# DSP_Block.net
KiCad netlist of a schematic drawn in Altium Designer
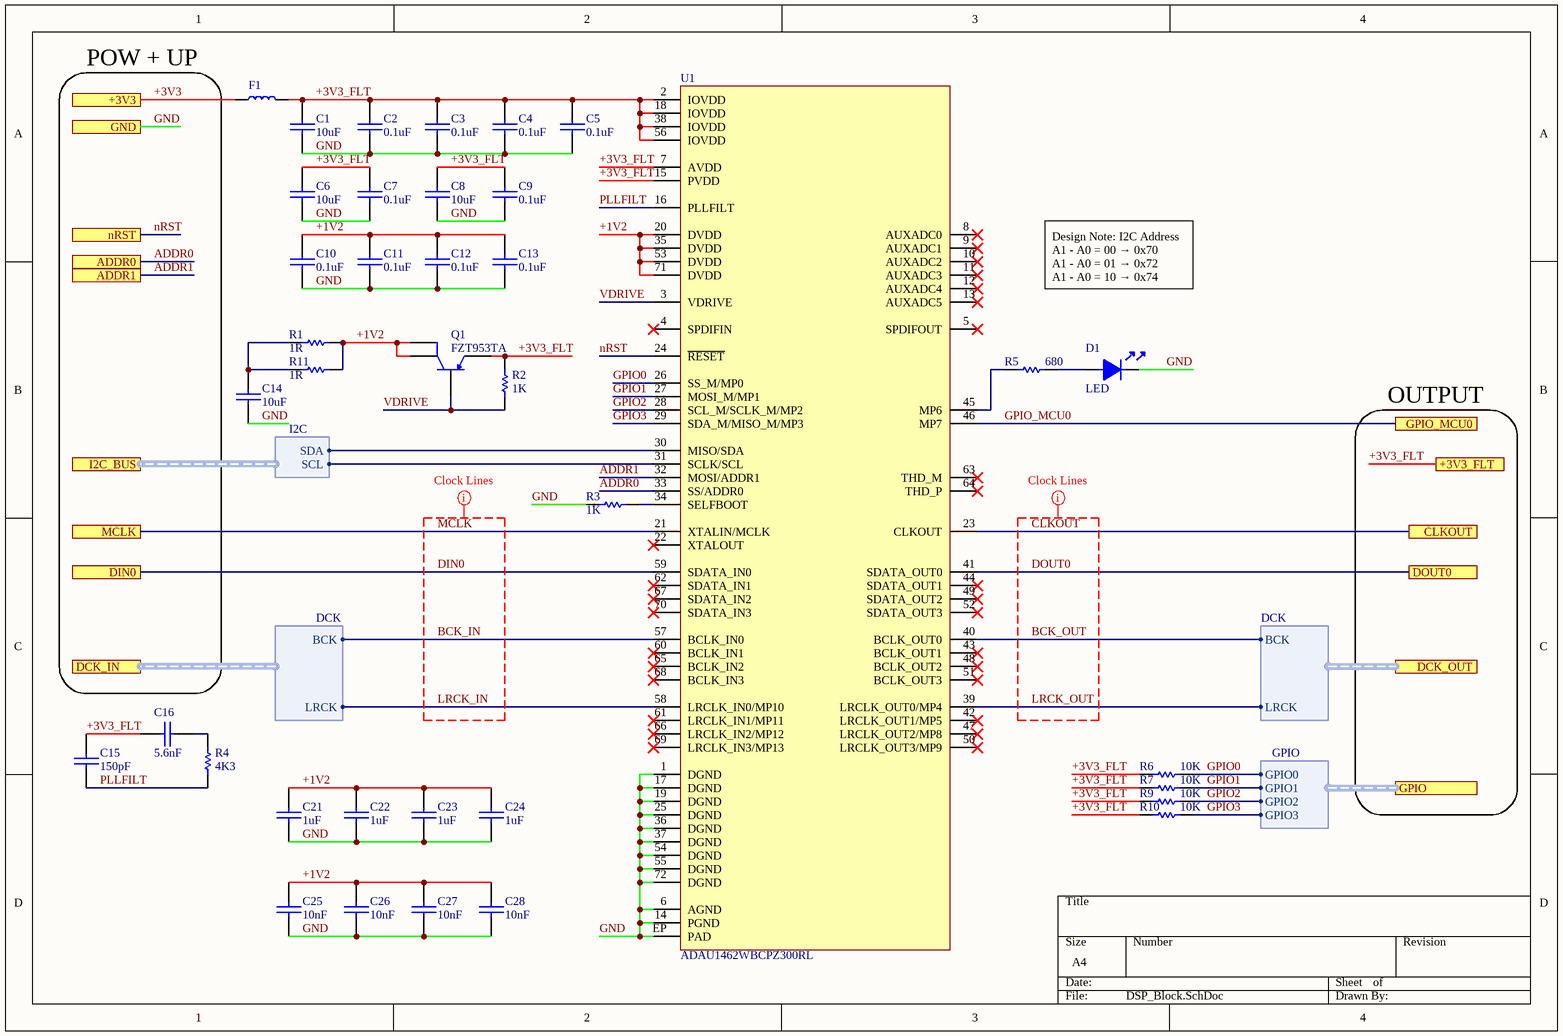
[diagram p0: DSP_Block.SchDoc]

(export (version "E")
  (design (tool "Eeschema 10.0.6"))
  (components
    (comp (ref "C1")
      (value "10uF")
      (footprint "0402-CAP-TDK")
      (fields (field (name "JLCPART") "C324476"))
      (libsource (lib "LIB2022 - Passives") (part "CAP-SMD"))
    )
    (comp (ref "C2")
      (value "0.1uF")
      (footprint "0402-CAP-TDK")
      (fields (field (name "JLCPART") "C307331"))
      (libsource (lib "LIB2022 - Passives") (part "CAP-SMD"))
    )
    (comp (ref "C3")
      (value "0.1uF")
      (footprint "0402-CAP-TDK")
      (fields (field (name "JLCPART") "C307331"))
      (libsource (lib "LIB2022 - Passives") (part "CAP-SMD"))
    )
    (comp (ref "C4")
      (value "0.1uF")
      (footprint "0402-CAP-TDK")
      (fields (field (name "JLCPART") "C307331"))
      (libsource (lib "LIB2022 - Passives") (part "CAP-SMD"))
    )
    (comp (ref "C5")
      (value "0.1uF")
      (footprint "0402-CAP-TDK")
      (fields (field (name "JLCPART") "C307331"))
      (libsource (lib "LIB2022 - Passives") (part "CAP-SMD"))
    )
    (comp (ref "C6")
      (value "10uF")
      (footprint "0402-CAP-TDK")
      (fields (field (name "JLCPART") "C324476"))
      (libsource (lib "LIB2022 - Passives") (part "CAP-SMD"))
    )
    (comp (ref "C7")
      (value "0.1uF")
      (footprint "0402-CAP-TDK")
      (fields (field (name "JLCPART") "C307331"))
      (libsource (lib "LIB2022 - Passives") (part "CAP-SMD"))
    )
    (comp (ref "C8")
      (value "10uF")
      (footprint "0402-CAP-TDK")
      (fields (field (name "JLCPART") "C324476"))
      (libsource (lib "LIB2022 - Passives") (part "CAP-SMD"))
    )
    (comp (ref "C9")
      (value "0.1uF")
      (footprint "0402-CAP-TDK")
      (fields (field (name "JLCPART") "C307331"))
      (libsource (lib "LIB2022 - Passives") (part "CAP-SMD"))
    )
    (comp (ref "C10")
      (value "0.1uF")
      (footprint "0402-CAP-TDK")
      (fields (field (name "JLCPART") "C307331"))
      (libsource (lib "LIB2022 - Passives") (part "CAP-SMD"))
    )
    (comp (ref "C11")
      (value "0.1uF")
      (footprint "0402-CAP-TDK")
      (fields (field (name "JLCPART") "C307331"))
      (libsource (lib "LIB2022 - Passives") (part "CAP-SMD"))
    )
    (comp (ref "C12")
      (value "0.1uF")
      (footprint "0402-CAP-TDK")
      (fields (field (name "JLCPART") "C307331"))
      (libsource (lib "LIB2022 - Passives") (part "CAP-SMD"))
    )
    (comp (ref "C13")
      (value "0.1uF")
      (footprint "0402-CAP-TDK")
      (fields (field (name "JLCPART") "C307331"))
      (libsource (lib "LIB2022 - Passives") (part "CAP-SMD"))
    )
    (comp (ref "C14")
      (value "10uF")
      (footprint "0402-CAP-TDK")
      (fields (field (name "JLCPART") "C324476"))
      (libsource (lib "LIB2022 - Passives") (part "CAP-SMD"))
    )
    (comp (ref "C15")
      (value "150pF")
      (footprint "0402-CAP-TDK")
      (fields (field (name "JLCPART") "C237333"))
      (libsource (lib "LIB2022 - Passives") (part "CAP-SMD"))
    )
    (comp (ref "C16")
      (value "5.6nF")
      (footprint "0402-CAP-TDK")
      (fields (field (name "JLCPART") "C513725"))
      (libsource (lib "LIB2022 - Passives") (part "CAP-SMD"))
    )
    (comp (ref "C21")
      (value "1uF")
      (footprint "0402-CAP-TDK")
      (fields (field (name "JLCPART") "C52923"))
      (libsource (lib "LIB2022 - Passives") (part "CAP-SMD"))
    )
    (comp (ref "C22")
      (value "1uF")
      (footprint "0402-CAP-TDK")
      (fields (field (name "JLCPART") "C52923"))
      (libsource (lib "LIB2022 - Passives") (part "CAP-SMD"))
    )
    (comp (ref "C23")
      (value "1uF")
      (footprint "0402-CAP-TDK")
      (fields (field (name "JLCPART") "C52923"))
      (libsource (lib "LIB2022 - Passives") (part "CAP-SMD"))
    )
    (comp (ref "C24")
      (value "1uF")
      (footprint "0402-CAP-TDK")
      (fields (field (name "JLCPART") "C52923"))
      (libsource (lib "LIB2022 - Passives") (part "CAP-SMD"))
    )
    (comp (ref "C25")
      (value "10nF")
      (footprint "0402-CAP-TDK")
      (fields (field (name "JLCPART") "C15195"))
      (libsource (lib "LIB2022 - Passives") (part "CAP-SMD"))
    )
    (comp (ref "C26")
      (value "10nF")
      (footprint "0402-CAP-TDK")
      (fields (field (name "JLCPART") "C15195"))
      (libsource (lib "LIB2022 - Passives") (part "CAP-SMD"))
    )
    (comp (ref "C27")
      (value "10nF")
      (footprint "0402-CAP-TDK")
      (fields (field (name "JLCPART") "C15195"))
      (libsource (lib "LIB2022 - Passives") (part "CAP-SMD"))
    )
    (comp (ref "C28")
      (value "10nF")
      (footprint "0402-CAP-TDK")
      (fields (field (name "JLCPART") "C15195"))
      (libsource (lib "LIB2022 - Passives") (part "CAP-SMD"))
    )
    (comp (ref "D1")
      (value "LED")
      (footprint "LED-0805")
      (fields (field (name "JLCPART") "C84256"))
      (libsource (lib "LIB2022 - Optoelectronics") (part "LED-SMD"))
    )
    (comp (ref "F1")
      (value "BLM18PG181SN1D")
      (footprint "0603-IND-MURATA")
      (description "90mΩ ±25% 180Ω@100MHz 1.5A - 0603")
      (fields (field (name "JLCPART") "C82850"))
      (libsource (lib "LIB2022 - Filters") (part "BLM18PG181SN1D"))
    )
    (comp (ref "Q1")
      (value "FZT953TA")
      (footprint "SOT223-DN")
      (description "Bipolar (BJT) Transistor PNP 100 V 5 A 120MHz 3 W Surface Mount SOT-223-3")
      (fields (field (name "JLCPART") "C110507"))
      (libsource (lib "LIB2022 - Semiconductors") (part "FZT953TA"))
    )
    (comp (ref "R1")
      (value "1R")
      (footprint "0603-RES-PANASONIC")
      (fields (field (name "JLCPART") "C22936"))
      (libsource (lib "LIB2022 - Passives") (part "RES-SMD"))
    )
    (comp (ref "R2")
      (value "1K")
      (footprint "0402-RES-PANASONIC")
      (fields (field (name "JLCPART") "C11702"))
      (libsource (lib "LIB2022 - Passives") (part "RES-SMD"))
    )
    (comp (ref "R3")
      (value "1K")
      (footprint "0402-RES-PANASONIC")
      (fields (field (name "JLCPART") "C11702"))
      (libsource (lib "LIB2022 - Passives") (part "RES-SMD"))
    )
    (comp (ref "R4")
      (value "4K3")
      (footprint "0402-RES-PANASONIC")
      (fields (field (name "JLCPART") "C477725"))
      (libsource (lib "LIB2022 - Passives") (part "RES-SMD"))
    )
    (comp (ref "R5")
      (value "680")
      (footprint "0402-RES-PANASONIC")
      (fields (field (name "JLCPART") "C25130"))
      (libsource (lib "LIB2022 - Passives") (part "RES-SMD"))
    )
    (comp (ref "R6")
      (value "10K")
      (footprint "0402-RES-PANASONIC")
      (fields (field (name "JLCPART") "C25744"))
      (libsource (lib "LIB2022 - Passives") (part "RES-SMD"))
    )
    (comp (ref "R7")
      (value "10K")
      (footprint "0402-RES-PANASONIC")
      (fields (field (name "JLCPART") "C25744"))
      (libsource (lib "LIB2022 - Passives") (part "RES-SMD"))
    )
    (comp (ref "R9")
      (value "10K")
      (footprint "0402-RES-PANASONIC")
      (fields (field (name "JLCPART") "C25744"))
      (libsource (lib "LIB2022 - Passives") (part "RES-SMD"))
    )
    (comp (ref "R10")
      (value "10K")
      (footprint "0402-RES-PANASONIC")
      (fields (field (name "JLCPART") "C25744"))
      (libsource (lib "LIB2022 - Passives") (part "RES-SMD"))
    )
    (comp (ref "R11")
      (value "1R")
      (footprint "0603-RES-PANASONIC")
      (fields (field (name "JLCPART") "C22936"))
      (libsource (lib "LIB2022 - Passives") (part "RES-SMD"))
    )
    (comp (ref "U1")
      (value "ADAU1462WBCPZ300RL")
      (footprint "LFCSP-VQ-72")
      (description "SigmaDSP 294.912 MHz, 32-bit Audio Processor")
      (fields (field (name "JLCPART") "C654408"))
      (libsource (lib "LIB2022 - ICs") (part "ADAU1462WBCPZ300RL"))
    )
  )
  (nets
    (net (code "4") (name "/+1V2") (class "Default")
      (node (ref "C10") (pin "2") (pinfunction "2_2") (pintype "passive"))
      (node (ref "C11") (pin "2") (pinfunction "2_2") (pintype "passive"))
      (node (ref "C12") (pin "2") (pinfunction "2_2") (pintype "passive"))
      (node (ref "C13") (pin "2") (pinfunction "2_2") (pintype "passive"))
      (node (ref "C21") (pin "2") (pinfunction "2_2") (pintype "passive"))
      (node (ref "C22") (pin "2") (pinfunction "2_2") (pintype "passive"))
      (node (ref "C23") (pin "2") (pinfunction "2_2") (pintype "passive"))
      (node (ref "C24") (pin "2") (pinfunction "2_2") (pintype "passive"))
      (node (ref "C25") (pin "2") (pinfunction "2_2") (pintype "passive"))
      (node (ref "C26") (pin "2") (pinfunction "2_2") (pintype "passive"))
      (node (ref "C27") (pin "2") (pinfunction "2_2") (pintype "passive"))
      (node (ref "C28") (pin "2") (pinfunction "2_2") (pintype "passive"))
      (node (ref "Q1") (pin "C") (pinfunction "C_C") (pintype "passive"))
      (node (ref "Q1") (pin "C-TAB") (pinfunction "C-TAB_C-TAB") (pintype "passive"))
      (node (ref "R1") (pin "1") (pinfunction "1_1") (pintype "passive"))
      (node (ref "R11") (pin "1") (pinfunction "1_1") (pintype "passive"))
      (node (ref "U1") (pin "20") (pinfunction "DVDD_20") (pintype "passive"))
      (node (ref "U1") (pin "35") (pinfunction "DVDD_35") (pintype "passive"))
      (node (ref "U1") (pin "53") (pinfunction "DVDD_53") (pintype "passive"))
      (node (ref "U1") (pin "71") (pinfunction "DVDD_71") (pintype "passive"))
    )
    (net (code "5") (name "/+3V3") (class "Default")
      (node (ref "F1") (pin "2") (pinfunction "2_2") (pintype "passive"))
    )
    (net (code "6") (name "/+3V3_FLT") (class "Default")
      (node (ref "C1") (pin "2") (pinfunction "2_2") (pintype "passive"))
      (node (ref "C15") (pin "2") (pinfunction "2_2") (pintype "passive"))
      (node (ref "C16") (pin "2") (pinfunction "2_2") (pintype "passive"))
      (node (ref "C2") (pin "2") (pinfunction "2_2") (pintype "passive"))
      (node (ref "C3") (pin "2") (pinfunction "2_2") (pintype "passive"))
      (node (ref "C4") (pin "2") (pinfunction "2_2") (pintype "passive"))
      (node (ref "C5") (pin "2") (pinfunction "2_2") (pintype "passive"))
      (node (ref "C6") (pin "2") (pinfunction "2_2") (pintype "passive"))
      (node (ref "C7") (pin "2") (pinfunction "2_2") (pintype "passive"))
      (node (ref "C8") (pin "2") (pinfunction "2_2") (pintype "passive"))
      (node (ref "C9") (pin "2") (pinfunction "2_2") (pintype "passive"))
      (node (ref "F1") (pin "1") (pinfunction "1_1") (pintype "passive"))
      (node (ref "Q1") (pin "E") (pinfunction "E_E") (pintype "passive"))
      (node (ref "R10") (pin "2") (pinfunction "2_2") (pintype "passive"))
      (node (ref "R2") (pin "2") (pinfunction "2_2") (pintype "passive"))
      (node (ref "R6") (pin "1") (pinfunction "1_1") (pintype "passive"))
      (node (ref "R7") (pin "2") (pinfunction "2_2") (pintype "passive"))
      (node (ref "R9") (pin "1") (pinfunction "1_1") (pintype "passive"))
      (node (ref "U1") (pin "15") (pinfunction "PVDD_15") (pintype "passive"))
      (node (ref "U1") (pin "18") (pinfunction "IOVDD_18") (pintype "passive"))
      (node (ref "U1") (pin "2") (pinfunction "IOVDD_2") (pintype "passive"))
      (node (ref "U1") (pin "38") (pinfunction "IOVDD_38") (pintype "passive"))
      (node (ref "U1") (pin "56") (pinfunction "IOVDD_56") (pintype "passive"))
      (node (ref "U1") (pin "7") (pinfunction "AVDD_7") (pintype "passive"))
    )
    (net (code "7") (name "/ADDR0") (class "Default")
      (node (ref "U1") (pin "33") (pinfunction "SS/ADDR0_33") (pintype "passive"))
    )
    (net (code "8") (name "/ADDR1") (class "Default")
      (node (ref "U1") (pin "32") (pinfunction "MOSI/ADDR1_32") (pintype "passive"))
    )
    (net (code "9") (name "/BCK_IN") (class "Default")
      (node (ref "U1") (pin "57") (pinfunction "BCLK_IN0_57") (pintype "passive"))
    )
    (net (code "10") (name "/BCK_OUT") (class "Default")
      (node (ref "U1") (pin "40") (pinfunction "BCLK_OUT0_40") (pintype "passive"))
    )
    (net (code "11") (name "/CLKOUT") (class "Default")
      (node (ref "U1") (pin "23") (pinfunction "CLKOUT_23") (pintype "passive"))
    )
    (net (code "12") (name "/DIN0") (class "Default")
      (node (ref "U1") (pin "59") (pinfunction "SDATA_IN0_59") (pintype "passive"))
    )
    (net (code "13") (name "/DOUT0") (class "Default")
      (node (ref "U1") (pin "41") (pinfunction "SDATA_OUT0_41") (pintype "passive"))
    )
    (net (code "14") (name "/GND") (class "Default")
      (node (ref "C1") (pin "1") (pinfunction "1_1") (pintype "passive"))
      (node (ref "C10") (pin "1") (pinfunction "1_1") (pintype "passive"))
      (node (ref "C11") (pin "1") (pinfunction "1_1") (pintype "passive"))
      (node (ref "C12") (pin "1") (pinfunction "1_1") (pintype "passive"))
      (node (ref "C13") (pin "1") (pinfunction "1_1") (pintype "passive"))
      (node (ref "C14") (pin "1") (pinfunction "1_1") (pintype "passive"))
      (node (ref "C2") (pin "1") (pinfunction "1_1") (pintype "passive"))
      (node (ref "C21") (pin "1") (pinfunction "1_1") (pintype "passive"))
      (node (ref "C22") (pin "1") (pinfunction "1_1") (pintype "passive"))
      (node (ref "C23") (pin "1") (pinfunction "1_1") (pintype "passive"))
      (node (ref "C24") (pin "1") (pinfunction "1_1") (pintype "passive"))
      (node (ref "C25") (pin "1") (pinfunction "1_1") (pintype "passive"))
      (node (ref "C26") (pin "1") (pinfunction "1_1") (pintype "passive"))
      (node (ref "C27") (pin "1") (pinfunction "1_1") (pintype "passive"))
      (node (ref "C28") (pin "1") (pinfunction "1_1") (pintype "passive"))
      (node (ref "C3") (pin "1") (pinfunction "1_1") (pintype "passive"))
      (node (ref "C4") (pin "1") (pinfunction "1_1") (pintype "passive"))
      (node (ref "C5") (pin "1") (pinfunction "1_1") (pintype "passive"))
      (node (ref "C6") (pin "1") (pinfunction "1_1") (pintype "passive"))
      (node (ref "C7") (pin "1") (pinfunction "1_1") (pintype "passive"))
      (node (ref "C8") (pin "1") (pinfunction "1_1") (pintype "passive"))
      (node (ref "C9") (pin "1") (pinfunction "1_1") (pintype "passive"))
      (node (ref "D1") (pin "2") (pinfunction "2_2") (pintype "passive"))
      (node (ref "R3") (pin "2") (pinfunction "2_2") (pintype "passive"))
      (node (ref "U1") (pin "1") (pinfunction "DGND_1") (pintype "passive"))
      (node (ref "U1") (pin "14") (pinfunction "PGND_14") (pintype "passive"))
      (node (ref "U1") (pin "17") (pinfunction "DGND_17") (pintype "passive"))
      (node (ref "U1") (pin "19") (pinfunction "DGND_19") (pintype "passive"))
      (node (ref "U1") (pin "25") (pinfunction "DGND_25") (pintype "passive"))
      (node (ref "U1") (pin "36") (pinfunction "DGND_36") (pintype "passive"))
      (node (ref "U1") (pin "37") (pinfunction "DGND_37") (pintype "passive"))
      (node (ref "U1") (pin "54") (pinfunction "DGND_54") (pintype "passive"))
      (node (ref "U1") (pin "55") (pinfunction "DGND_55") (pintype "passive"))
      (node (ref "U1") (pin "6") (pinfunction "AGND_6") (pintype "passive"))
      (node (ref "U1") (pin "72") (pinfunction "DGND_72") (pintype "passive"))
      (node (ref "U1") (pin "EP") (pinfunction "PAD_EP") (pintype "passive"))
    )
    (net (code "15") (name "/GPIO0") (class "Default")
      (node (ref "R6") (pin "2") (pinfunction "2_2") (pintype "passive"))
      (node (ref "U1") (pin "26") (pinfunction "SS_M/MP0_26") (pintype "passive"))
    )
    (net (code "16") (name "/GPIO1") (class "Default")
      (node (ref "R7") (pin "1") (pinfunction "1_1") (pintype "passive"))
      (node (ref "U1") (pin "27") (pinfunction "MOSI_M/MP1_27") (pintype "passive"))
    )
    (net (code "17") (name "/GPIO2") (class "Default")
      (node (ref "R9") (pin "2") (pinfunction "2_2") (pintype "passive"))
      (node (ref "U1") (pin "28") (pinfunction "SCL_M/SCLK_M/MP2_28") (pintype "passive"))
    )
    (net (code "18") (name "/GPIO3") (class "Default")
      (node (ref "R10") (pin "1") (pinfunction "1_1") (pintype "passive"))
      (node (ref "U1") (pin "29") (pinfunction "SDA_M/MISO_M/MP3_29") (pintype "passive"))
    )
    (net (code "19") (name "/GPIO_MCU0") (class "Default")
      (node (ref "U1") (pin "46") (pinfunction "MP7_46") (pintype "passive"))
    )
    (net (code "20") (name "/LRCK_IN") (class "Default")
      (node (ref "U1") (pin "58") (pinfunction "LRCLK_IN0/MP10_58") (pintype "passive"))
    )
    (net (code "21") (name "/LRCK_OUT") (class "Default")
      (node (ref "U1") (pin "39") (pinfunction "LRCLK_OUT0/MP4_39") (pintype "passive"))
    )
    (net (code "22") (name "/MCLK") (class "Default")
      (node (ref "U1") (pin "21") (pinfunction "XTALIN/MCLK_21") (pintype "passive"))
    )
    (net (code "23") (name "/PLLFILT") (class "Default")
      (node (ref "C15") (pin "1") (pinfunction "1_1") (pintype "passive"))
      (node (ref "R4") (pin "1") (pinfunction "1_1") (pintype "passive"))
      (node (ref "U1") (pin "16") (pinfunction "PLLFILT_16") (pintype "passive"))
    )
    (net (code "24") (name "/SCL") (class "Default")
      (node (ref "U1") (pin "31") (pinfunction "SCLK/SCL_31") (pintype "passive"))
    )
    (net (code "25") (name "/SDA") (class "Default")
      (node (ref "U1") (pin "30") (pinfunction "MISO/SDA_30") (pintype "passive"))
    )
    (net (code "26") (name "/VDRIVE") (class "Default")
      (node (ref "Q1") (pin "B") (pinfunction "B_B") (pintype "passive"))
      (node (ref "R2") (pin "1") (pinfunction "1_1") (pintype "passive"))
      (node (ref "U1") (pin "3") (pinfunction "VDRIVE_3") (pintype "passive"))
    )
    (net (code "27") (name "/nRST") (class "Default")
      (node (ref "U1") (pin "24") (pinfunction "~{RESET}_24") (pintype "passive"))
    )
    (net (code "31") (name "Net-(C14-Pad2)") (class "Default")
      (node (ref "C14") (pin "2") (pinfunction "2_2") (pintype "passive"))
      (node (ref "R1") (pin "2") (pinfunction "2_2") (pintype "passive"))
      (node (ref "R11") (pin "2") (pinfunction "2_2") (pintype "passive"))
    )
    (net (code "32") (name "Net-(C16-Pad1)") (class "Default")
      (node (ref "C16") (pin "1") (pinfunction "1_1") (pintype "passive"))
      (node (ref "R4") (pin "2") (pinfunction "2_2") (pintype "passive"))
    )
    (net (code "33") (name "Net-(D1-Pad1)") (class "Default")
      (node (ref "D1") (pin "1") (pinfunction "1_1") (pintype "passive"))
      (node (ref "R5") (pin "2") (pinfunction "2_2") (pintype "passive"))
    )
    (net (code "34") (name "Net-(U1-MP6)") (class "Default")
      (node (ref "R5") (pin "1") (pinfunction "1_1") (pintype "passive"))
      (node (ref "U1") (pin "45") (pinfunction "MP6_45") (pintype "passive"))
    )
    (net (code "35") (name "Net-(U1-SELFBOOT)") (class "Default")
      (node (ref "R3") (pin "1") (pinfunction "1_1") (pintype "passive"))
      (node (ref "U1") (pin "34") (pinfunction "SELFBOOT_34") (pintype "passive"))
    )
    (net (code "36") (name "unconnected-(U1-AUXADC0-Pad8)") (class "Default")
      (node (ref "U1") (pin "8") (pinfunction "AUXADC0_8") (pintype "passive+no_connect"))
    )
    (net (code "37") (name "unconnected-(U1-AUXADC1-Pad9)") (class "Default")
      (node (ref "U1") (pin "9") (pinfunction "AUXADC1_9") (pintype "passive+no_connect"))
    )
    (net (code "38") (name "unconnected-(U1-AUXADC2-Pad10)") (class "Default")
      (node (ref "U1") (pin "10") (pinfunction "AUXADC2_10") (pintype "passive+no_connect"))
    )
    (net (code "39") (name "unconnected-(U1-AUXADC3-Pad11)") (class "Default")
      (node (ref "U1") (pin "11") (pinfunction "AUXADC3_11") (pintype "passive+no_connect"))
    )
    (net (code "40") (name "unconnected-(U1-AUXADC4-Pad12)") (class "Default")
      (node (ref "U1") (pin "12") (pinfunction "AUXADC4_12") (pintype "passive+no_connect"))
    )
    (net (code "41") (name "unconnected-(U1-AUXADC5-Pad13)") (class "Default")
      (node (ref "U1") (pin "13") (pinfunction "AUXADC5_13") (pintype "passive+no_connect"))
    )
    (net (code "42") (name "unconnected-(U1-BCLK_IN1-Pad60)") (class "Default")
      (node (ref "U1") (pin "60") (pinfunction "BCLK_IN1_60") (pintype "passive+no_connect"))
    )
    (net (code "43") (name "unconnected-(U1-BCLK_IN2-Pad65)") (class "Default")
      (node (ref "U1") (pin "65") (pinfunction "BCLK_IN2_65") (pintype "passive+no_connect"))
    )
    (net (code "44") (name "unconnected-(U1-BCLK_IN3-Pad68)") (class "Default")
      (node (ref "U1") (pin "68") (pinfunction "BCLK_IN3_68") (pintype "passive+no_connect"))
    )
    (net (code "45") (name "unconnected-(U1-BCLK_OUT1-Pad43)") (class "Default")
      (node (ref "U1") (pin "43") (pinfunction "BCLK_OUT1_43") (pintype "passive+no_connect"))
    )
    (net (code "46") (name "unconnected-(U1-BCLK_OUT2-Pad48)") (class "Default")
      (node (ref "U1") (pin "48") (pinfunction "BCLK_OUT2_48") (pintype "passive+no_connect"))
    )
    (net (code "47") (name "unconnected-(U1-BCLK_OUT3-Pad51)") (class "Default")
      (node (ref "U1") (pin "51") (pinfunction "BCLK_OUT3_51") (pintype "passive+no_connect"))
    )
    (net (code "48") (name "unconnected-(U1-LRCLK_IN1{slash}MP11-Pad61)") (class "Default")
      (node (ref "U1") (pin "61") (pinfunction "LRCLK_IN1/MP11_61") (pintype "passive+no_connect"))
    )
    (net (code "49") (name "unconnected-(U1-LRCLK_IN2{slash}MP12-Pad66)") (class "Default")
      (node (ref "U1") (pin "66") (pinfunction "LRCLK_IN2/MP12_66") (pintype "passive+no_connect"))
    )
    (net (code "50") (name "unconnected-(U1-LRCLK_IN3{slash}MP13-Pad69)") (class "Default")
      (node (ref "U1") (pin "69") (pinfunction "LRCLK_IN3/MP13_69") (pintype "passive+no_connect"))
    )
    (net (code "51") (name "unconnected-(U1-LRCLK_OUT1{slash}MP5-Pad42)") (class "Default")
      (node (ref "U1") (pin "42") (pinfunction "LRCLK_OUT1/MP5_42") (pintype "passive+no_connect"))
    )
    (net (code "52") (name "unconnected-(U1-LRCLK_OUT2{slash}MP8-Pad47)") (class "Default")
      (node (ref "U1") (pin "47") (pinfunction "LRCLK_OUT2/MP8_47") (pintype "passive+no_connect"))
    )
    (net (code "53") (name "unconnected-(U1-LRCLK_OUT3{slash}MP9-Pad50)") (class "Default")
      (node (ref "U1") (pin "50") (pinfunction "LRCLK_OUT3/MP9_50") (pintype "passive+no_connect"))
    )
    (net (code "54") (name "unconnected-(U1-SDATA_IN1-Pad62)") (class "Default")
      (node (ref "U1") (pin "62") (pinfunction "SDATA_IN1_62") (pintype "passive+no_connect"))
    )
    (net (code "55") (name "unconnected-(U1-SDATA_IN2-Pad67)") (class "Default")
      (node (ref "U1") (pin "67") (pinfunction "SDATA_IN2_67") (pintype "passive+no_connect"))
    )
    (net (code "56") (name "unconnected-(U1-SDATA_IN3-Pad70)") (class "Default")
      (node (ref "U1") (pin "70") (pinfunction "SDATA_IN3_70") (pintype "passive+no_connect"))
    )
    (net (code "57") (name "unconnected-(U1-SDATA_OUT1-Pad44)") (class "Default")
      (node (ref "U1") (pin "44") (pinfunction "SDATA_OUT1_44") (pintype "passive+no_connect"))
    )
    (net (code "58") (name "unconnected-(U1-SDATA_OUT2-Pad49)") (class "Default")
      (node (ref "U1") (pin "49") (pinfunction "SDATA_OUT2_49") (pintype "passive+no_connect"))
    )
    (net (code "59") (name "unconnected-(U1-SDATA_OUT3-Pad52)") (class "Default")
      (node (ref "U1") (pin "52") (pinfunction "SDATA_OUT3_52") (pintype "passive+no_connect"))
    )
    (net (code "60") (name "unconnected-(U1-SPDIFIN-Pad4)") (class "Default")
      (node (ref "U1") (pin "4") (pinfunction "SPDIFIN_4") (pintype "passive+no_connect"))
    )
    (net (code "61") (name "unconnected-(U1-SPDIFOUT-Pad5)") (class "Default")
      (node (ref "U1") (pin "5") (pinfunction "SPDIFOUT_5") (pintype "passive+no_connect"))
    )
    (net (code "62") (name "unconnected-(U1-THD_M-Pad63)") (class "Default")
      (node (ref "U1") (pin "63") (pinfunction "THD_M_63") (pintype "passive+no_connect"))
    )
    (net (code "63") (name "unconnected-(U1-THD_P-Pad64)") (class "Default")
      (node (ref "U1") (pin "64") (pinfunction "THD_P_64") (pintype "passive+no_connect"))
    )
    (net (code "64") (name "unconnected-(U1-XTALOUT-Pad22)") (class "Default")
      (node (ref "U1") (pin "22") (pinfunction "XTALOUT_22") (pintype "passive+no_connect"))
    )
  )
)
